# geiger_01_detect.net
KiCad netlist of a schematic drawn in EAGLE
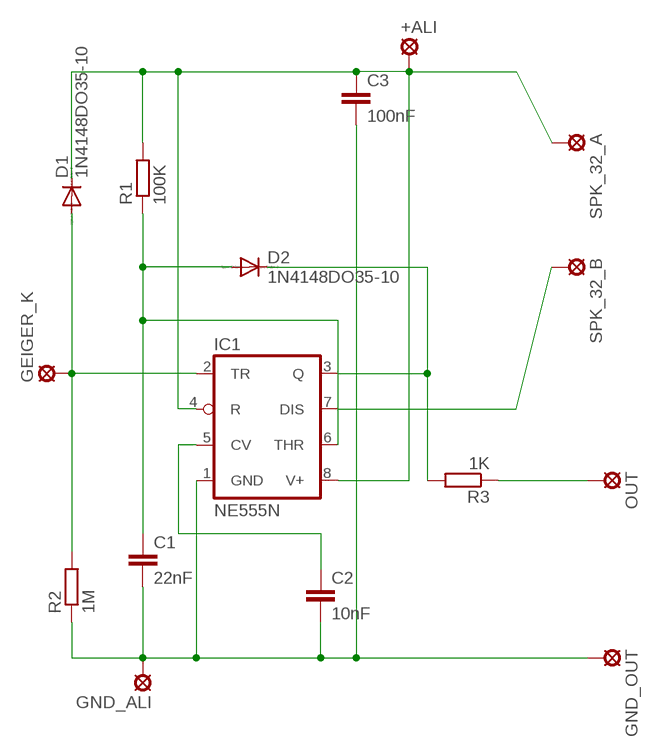
[diagram p0: schematic, sheet 1]

(export (version "E")
  (design (tool "Eeschema 10.0.6"))
  (components
    (comp (ref "+ALI")
      (value "LSP10")
      (footprint "eagle-import:LSP10")
      (libsource (lib "eagle-import") (part "LSP10"))
    )
    (comp (ref "C1")
      (value "22nF")
      (footprint "eagle-import:C050-025X075")
      (libsource (lib "eagle-import") (part "C-EU050-025X075"))
    )
    (comp (ref "C2")
      (value "10nF")
      (footprint "eagle-import:C050-025X075")
      (libsource (lib "eagle-import") (part "C-EU050-025X075"))
    )
    (comp (ref "C3")
      (value "100nF")
      (footprint "eagle-import:C050-025X075")
      (libsource (lib "eagle-import") (part "C-EU050-025X075"))
    )
    (comp (ref "D1")
      (value "1N4148DO35-10")
      (footprint "eagle-import:DO35-10")
      (libsource (lib "eagle-import") (part "1N4148DO35-10"))
    )
    (comp (ref "D2")
      (value "1N4148DO35-10")
      (footprint "eagle-import:DO35-10")
      (libsource (lib "eagle-import") (part "1N4148DO35-10"))
    )
    (comp (ref "GEIGER_K")
      (value "LSP10")
      (footprint "eagle-import:LSP10")
      (libsource (lib "eagle-import") (part "LSP10"))
    )
    (comp (ref "GND_ALI")
      (value "LSP10")
      (footprint "eagle-import:LSP10")
      (libsource (lib "eagle-import") (part "LSP10"))
    )
    (comp (ref "GND_OUT")
      (value "LSP10")
      (footprint "eagle-import:LSP10")
      (libsource (lib "eagle-import") (part "LSP10"))
    )
    (comp (ref "IC1")
      (value "NE555N")
      (footprint "eagle-import:DIL08")
      (libsource (lib "eagle-import") (part "555NNE"))
    )
    (comp (ref "OUT")
      (value "LSP10")
      (footprint "eagle-import:LSP10")
      (libsource (lib "eagle-import") (part "LSP10"))
    )
    (comp (ref "R1")
      (value "100K")
      (footprint "eagle-import:0207_12")
      (libsource (lib "eagle-import") (part "R-EU_0207/12"))
    )
    (comp (ref "R2")
      (value "1M")
      (footprint "eagle-import:0207_12")
      (libsource (lib "eagle-import") (part "R-EU_0207/12"))
    )
    (comp (ref "R3")
      (value "1K")
      (footprint "eagle-import:0207_12")
      (libsource (lib "eagle-import") (part "R-EU_0207/12"))
    )
    (comp (ref "SPK_32_A")
      (value "LSP10")
      (footprint "eagle-import:LSP10")
      (libsource (lib "eagle-import") (part "LSP10"))
    )
    (comp (ref "SPK_32_B")
      (value "LSP10")
      (footprint "eagle-import:LSP10")
      (libsource (lib "eagle-import") (part "LSP10"))
    )
  )
  (nets
    (net (code "1") (name "Net-(IC1-CV)") (class "Default")
      (node (ref "C2") (pin "1") (pinfunction "1_1") (pintype "passive"))
      (node (ref "IC1") (pin "5") (pinfunction "CV_5") (pintype "input"))
    )
    (net (code "2") (name "Net-(IC1-DIS)") (class "Default")
      (node (ref "IC1") (pin "7") (pinfunction "DIS_7") (pintype "input"))
      (node (ref "SPK_32_B") (pin "MP") (pinfunction "MP_MP") (pintype "passive"))
    )
    (net (code "3") (name "Net-(IC1-GND)") (class "Default")
      (node (ref "C1") (pin "2") (pinfunction "2_2") (pintype "passive"))
      (node (ref "C2") (pin "2") (pinfunction "2_2") (pintype "passive"))
      (node (ref "C3") (pin "2") (pinfunction "2_2") (pintype "passive"))
      (node (ref "GND_ALI") (pin "MP") (pinfunction "MP_MP") (pintype "passive"))
      (node (ref "GND_OUT") (pin "MP") (pinfunction "MP_MP") (pintype "passive"))
      (node (ref "IC1") (pin "1") (pinfunction "GND_1") (pintype "power_in"))
      (node (ref "R2") (pin "1") (pinfunction "1_1") (pintype "passive"))
    )
    (net (code "4") (name "Net-(IC1-Q)") (class "Default")
      (node (ref "D2") (pin "C") (pinfunction "C_C") (pintype "passive"))
      (node (ref "IC1") (pin "3") (pinfunction "Q_3") (pintype "output"))
      (node (ref "R3") (pin "2") (pinfunction "2_2") (pintype "passive"))
    )
    (net (code "5") (name "Net-(IC1-R)") (class "Default")
      (node (ref "+ALI") (pin "MP") (pinfunction "MP_MP") (pintype "passive"))
      (node (ref "C3") (pin "1") (pinfunction "1_1") (pintype "passive"))
      (node (ref "D1") (pin "C") (pinfunction "C_C") (pintype "passive"))
      (node (ref "IC1") (pin "4") (pinfunction "R_4") (pintype "input"))
      (node (ref "IC1") (pin "8") (pinfunction "V+_8") (pintype "power_in"))
      (node (ref "R1") (pin "2") (pinfunction "2_2") (pintype "passive"))
      (node (ref "SPK_32_A") (pin "MP") (pinfunction "MP_MP") (pintype "passive"))
    )
    (net (code "6") (name "Net-(IC1-THR)") (class "Default")
      (node (ref "C1") (pin "1") (pinfunction "1_1") (pintype "passive"))
      (node (ref "D2") (pin "A") (pinfunction "A_A") (pintype "passive"))
      (node (ref "IC1") (pin "6") (pinfunction "THR_6") (pintype "input"))
      (node (ref "R1") (pin "1") (pinfunction "1_1") (pintype "passive"))
    )
    (net (code "7") (name "Net-(IC1-TR)") (class "Default")
      (node (ref "D1") (pin "A") (pinfunction "A_A") (pintype "passive"))
      (node (ref "GEIGER_K") (pin "MP") (pinfunction "MP_MP") (pintype "passive"))
      (node (ref "IC1") (pin "2") (pinfunction "TR_2") (pintype "input"))
      (node (ref "R2") (pin "2") (pinfunction "2_2") (pintype "passive"))
    )
    (net (code "8") (name "Net-(OUT-PadMP)") (class "Default")
      (node (ref "OUT") (pin "MP") (pinfunction "MP_MP") (pintype "passive"))
      (node (ref "R3") (pin "1") (pinfunction "1_1") (pintype "passive"))
    )
  )
)
